# Ultrasonic_Array_8x8.net
KiCad netlist of a schematic drawn in EAGLE
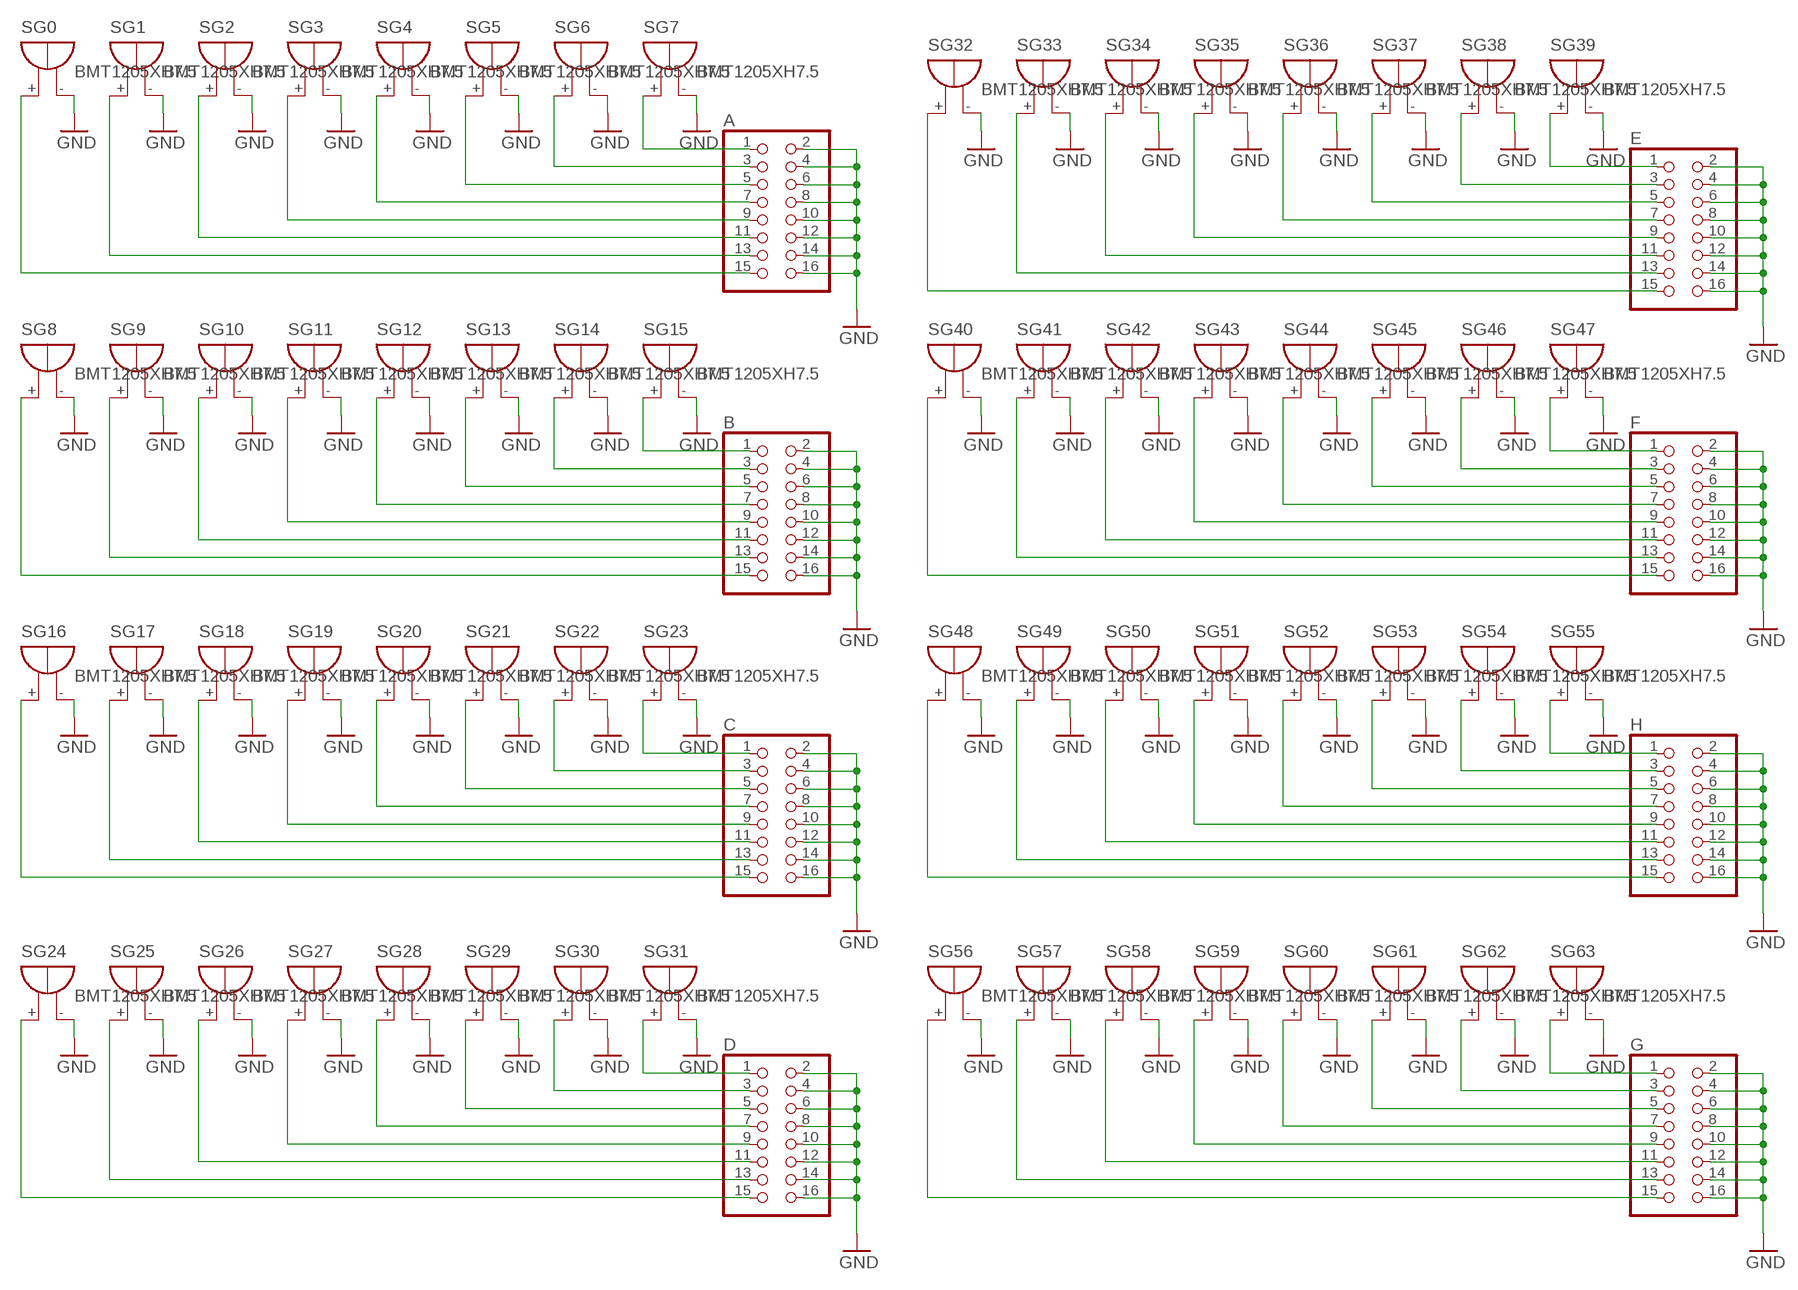
[diagram p0: schematic, sheet 1]

(export (version "E")
  (design (tool "Eeschema 10.0.6"))
  (components
    (comp (ref "A")
      (value "PINHD-2X8")
      (footprint "eagle-import:2X08")
      (libsource (lib "eagle-import") (part "PINHD-2X8"))
    )
    (comp (ref "B")
      (value "PINHD-2X8")
      (footprint "eagle-import:2X08")
      (libsource (lib "eagle-import") (part "PINHD-2X8"))
    )
    (comp (ref "C")
      (value "PINHD-2X8")
      (footprint "eagle-import:2X08")
      (libsource (lib "eagle-import") (part "PINHD-2X8"))
    )
    (comp (ref "D")
      (value "PINHD-2X8")
      (footprint "eagle-import:2X08")
      (libsource (lib "eagle-import") (part "PINHD-2X8"))
    )
    (comp (ref "E")
      (value "PINHD-2X8")
      (footprint "eagle-import:2X08")
      (libsource (lib "eagle-import") (part "PINHD-2X8"))
    )
    (comp (ref "F")
      (value "PINHD-2X8")
      (footprint "eagle-import:2X08")
      (libsource (lib "eagle-import") (part "PINHD-2X8"))
    )
    (comp (ref "G")
      (value "PINHD-2X8")
      (footprint "eagle-import:2X08")
      (libsource (lib "eagle-import") (part "PINHD-2X8"))
    )
    (comp (ref "H")
      (value "PINHD-2X8")
      (footprint "eagle-import:2X08")
      (libsource (lib "eagle-import") (part "PINHD-2X8"))
    )
    (comp (ref "SG0")
      (value "BMT1205XH7.5")
      (footprint "eagle-import:BMT1205XH7.5")
      (libsource (lib "eagle-import") (part "BMT1205XH7.5"))
    )
    (comp (ref "SG1")
      (value "BMT1205XH7.5")
      (footprint "eagle-import:BMT1205XH7.5")
      (libsource (lib "eagle-import") (part "BMT1205XH7.5"))
    )
    (comp (ref "SG2")
      (value "BMT1205XH7.5")
      (footprint "eagle-import:BMT1205XH7.5")
      (libsource (lib "eagle-import") (part "BMT1205XH7.5"))
    )
    (comp (ref "SG3")
      (value "BMT1205XH7.5")
      (footprint "eagle-import:BMT1205XH7.5")
      (libsource (lib "eagle-import") (part "BMT1205XH7.5"))
    )
    (comp (ref "SG4")
      (value "BMT1205XH7.5")
      (footprint "eagle-import:BMT1205XH7.5")
      (libsource (lib "eagle-import") (part "BMT1205XH7.5"))
    )
    (comp (ref "SG5")
      (value "BMT1205XH7.5")
      (footprint "eagle-import:BMT1205XH7.5")
      (libsource (lib "eagle-import") (part "BMT1205XH7.5"))
    )
    (comp (ref "SG6")
      (value "BMT1205XH7.5")
      (footprint "eagle-import:BMT1205XH7.5")
      (libsource (lib "eagle-import") (part "BMT1205XH7.5"))
    )
    (comp (ref "SG7")
      (value "BMT1205XH7.5")
      (footprint "eagle-import:BMT1205XH7.5")
      (libsource (lib "eagle-import") (part "BMT1205XH7.5"))
    )
    (comp (ref "SG8")
      (value "BMT1205XH7.5")
      (footprint "eagle-import:BMT1205XH7.5")
      (libsource (lib "eagle-import") (part "BMT1205XH7.5"))
    )
    (comp (ref "SG9")
      (value "BMT1205XH7.5")
      (footprint "eagle-import:BMT1205XH7.5")
      (libsource (lib "eagle-import") (part "BMT1205XH7.5"))
    )
    (comp (ref "SG10")
      (value "BMT1205XH7.5")
      (footprint "eagle-import:BMT1205XH7.5")
      (libsource (lib "eagle-import") (part "BMT1205XH7.5"))
    )
    (comp (ref "SG11")
      (value "BMT1205XH7.5")
      (footprint "eagle-import:BMT1205XH7.5")
      (libsource (lib "eagle-import") (part "BMT1205XH7.5"))
    )
    (comp (ref "SG12")
      (value "BMT1205XH7.5")
      (footprint "eagle-import:BMT1205XH7.5")
      (libsource (lib "eagle-import") (part "BMT1205XH7.5"))
    )
    (comp (ref "SG13")
      (value "BMT1205XH7.5")
      (footprint "eagle-import:BMT1205XH7.5")
      (libsource (lib "eagle-import") (part "BMT1205XH7.5"))
    )
    (comp (ref "SG14")
      (value "BMT1205XH7.5")
      (footprint "eagle-import:BMT1205XH7.5")
      (libsource (lib "eagle-import") (part "BMT1205XH7.5"))
    )
    (comp (ref "SG15")
      (value "BMT1205XH7.5")
      (footprint "eagle-import:BMT1205XH7.5")
      (libsource (lib "eagle-import") (part "BMT1205XH7.5"))
    )
    (comp (ref "SG16")
      (value "BMT1205XH7.5")
      (footprint "eagle-import:BMT1205XH7.5")
      (libsource (lib "eagle-import") (part "BMT1205XH7.5"))
    )
    (comp (ref "SG17")
      (value "BMT1205XH7.5")
      (footprint "eagle-import:BMT1205XH7.5")
      (libsource (lib "eagle-import") (part "BMT1205XH7.5"))
    )
    (comp (ref "SG18")
      (value "BMT1205XH7.5")
      (footprint "eagle-import:BMT1205XH7.5")
      (libsource (lib "eagle-import") (part "BMT1205XH7.5"))
    )
    (comp (ref "SG19")
      (value "BMT1205XH7.5")
      (footprint "eagle-import:BMT1205XH7.5")
      (libsource (lib "eagle-import") (part "BMT1205XH7.5"))
    )
    (comp (ref "SG20")
      (value "BMT1205XH7.5")
      (footprint "eagle-import:BMT1205XH7.5")
      (libsource (lib "eagle-import") (part "BMT1205XH7.5"))
    )
    (comp (ref "SG21")
      (value "BMT1205XH7.5")
      (footprint "eagle-import:BMT1205XH7.5")
      (libsource (lib "eagle-import") (part "BMT1205XH7.5"))
    )
    (comp (ref "SG22")
      (value "BMT1205XH7.5")
      (footprint "eagle-import:BMT1205XH7.5")
      (libsource (lib "eagle-import") (part "BMT1205XH7.5"))
    )
    (comp (ref "SG23")
      (value "BMT1205XH7.5")
      (footprint "eagle-import:BMT1205XH7.5")
      (libsource (lib "eagle-import") (part "BMT1205XH7.5"))
    )
    (comp (ref "SG24")
      (value "BMT1205XH7.5")
      (footprint "eagle-import:BMT1205XH7.5")
      (libsource (lib "eagle-import") (part "BMT1205XH7.5"))
    )
    (comp (ref "SG25")
      (value "BMT1205XH7.5")
      (footprint "eagle-import:BMT1205XH7.5")
      (libsource (lib "eagle-import") (part "BMT1205XH7.5"))
    )
    (comp (ref "SG26")
      (value "BMT1205XH7.5")
      (footprint "eagle-import:BMT1205XH7.5")
      (libsource (lib "eagle-import") (part "BMT1205XH7.5"))
    )
    (comp (ref "SG27")
      (value "BMT1205XH7.5")
      (footprint "eagle-import:BMT1205XH7.5")
      (libsource (lib "eagle-import") (part "BMT1205XH7.5"))
    )
    (comp (ref "SG28")
      (value "BMT1205XH7.5")
      (footprint "eagle-import:BMT1205XH7.5")
      (libsource (lib "eagle-import") (part "BMT1205XH7.5"))
    )
    (comp (ref "SG29")
      (value "BMT1205XH7.5")
      (footprint "eagle-import:BMT1205XH7.5")
      (libsource (lib "eagle-import") (part "BMT1205XH7.5"))
    )
    (comp (ref "SG30")
      (value "BMT1205XH7.5")
      (footprint "eagle-import:BMT1205XH7.5")
      (libsource (lib "eagle-import") (part "BMT1205XH7.5"))
    )
    (comp (ref "SG31")
      (value "BMT1205XH7.5")
      (footprint "eagle-import:BMT1205XH7.5")
      (libsource (lib "eagle-import") (part "BMT1205XH7.5"))
    )
    (comp (ref "SG32")
      (value "BMT1205XH7.5")
      (footprint "eagle-import:BMT1205XH7.5")
      (libsource (lib "eagle-import") (part "BMT1205XH7.5"))
    )
    (comp (ref "SG33")
      (value "BMT1205XH7.5")
      (footprint "eagle-import:BMT1205XH7.5")
      (libsource (lib "eagle-import") (part "BMT1205XH7.5"))
    )
    (comp (ref "SG34")
      (value "BMT1205XH7.5")
      (footprint "eagle-import:BMT1205XH7.5")
      (libsource (lib "eagle-import") (part "BMT1205XH7.5"))
    )
    (comp (ref "SG35")
      (value "BMT1205XH7.5")
      (footprint "eagle-import:BMT1205XH7.5")
      (libsource (lib "eagle-import") (part "BMT1205XH7.5"))
    )
    (comp (ref "SG36")
      (value "BMT1205XH7.5")
      (footprint "eagle-import:BMT1205XH7.5")
      (libsource (lib "eagle-import") (part "BMT1205XH7.5"))
    )
    (comp (ref "SG37")
      (value "BMT1205XH7.5")
      (footprint "eagle-import:BMT1205XH7.5")
      (libsource (lib "eagle-import") (part "BMT1205XH7.5"))
    )
    (comp (ref "SG38")
      (value "BMT1205XH7.5")
      (footprint "eagle-import:BMT1205XH7.5")
      (libsource (lib "eagle-import") (part "BMT1205XH7.5"))
    )
    (comp (ref "SG39")
      (value "BMT1205XH7.5")
      (footprint "eagle-import:BMT1205XH7.5")
      (libsource (lib "eagle-import") (part "BMT1205XH7.5"))
    )
    (comp (ref "SG40")
      (value "BMT1205XH7.5")
      (footprint "eagle-import:BMT1205XH7.5")
      (libsource (lib "eagle-import") (part "BMT1205XH7.5"))
    )
    (comp (ref "SG41")
      (value "BMT1205XH7.5")
      (footprint "eagle-import:BMT1205XH7.5")
      (libsource (lib "eagle-import") (part "BMT1205XH7.5"))
    )
    (comp (ref "SG42")
      (value "BMT1205XH7.5")
      (footprint "eagle-import:BMT1205XH7.5")
      (libsource (lib "eagle-import") (part "BMT1205XH7.5"))
    )
    (comp (ref "SG43")
      (value "BMT1205XH7.5")
      (footprint "eagle-import:BMT1205XH7.5")
      (libsource (lib "eagle-import") (part "BMT1205XH7.5"))
    )
    (comp (ref "SG44")
      (value "BMT1205XH7.5")
      (footprint "eagle-import:BMT1205XH7.5")
      (libsource (lib "eagle-import") (part "BMT1205XH7.5"))
    )
    (comp (ref "SG45")
      (value "BMT1205XH7.5")
      (footprint "eagle-import:BMT1205XH7.5")
      (libsource (lib "eagle-import") (part "BMT1205XH7.5"))
    )
    (comp (ref "SG46")
      (value "BMT1205XH7.5")
      (footprint "eagle-import:BMT1205XH7.5")
      (libsource (lib "eagle-import") (part "BMT1205XH7.5"))
    )
    (comp (ref "SG47")
      (value "BMT1205XH7.5")
      (footprint "eagle-import:BMT1205XH7.5")
      (libsource (lib "eagle-import") (part "BMT1205XH7.5"))
    )
    (comp (ref "SG48")
      (value "BMT1205XH7.5")
      (footprint "eagle-import:BMT1205XH7.5")
      (libsource (lib "eagle-import") (part "BMT1205XH7.5"))
    )
    (comp (ref "SG49")
      (value "BMT1205XH7.5")
      (footprint "eagle-import:BMT1205XH7.5")
      (libsource (lib "eagle-import") (part "BMT1205XH7.5"))
    )
    (comp (ref "SG50")
      (value "BMT1205XH7.5")
      (footprint "eagle-import:BMT1205XH7.5")
      (libsource (lib "eagle-import") (part "BMT1205XH7.5"))
    )
    (comp (ref "SG51")
      (value "BMT1205XH7.5")
      (footprint "eagle-import:BMT1205XH7.5")
      (libsource (lib "eagle-import") (part "BMT1205XH7.5"))
    )
    (comp (ref "SG52")
      (value "BMT1205XH7.5")
      (footprint "eagle-import:BMT1205XH7.5")
      (libsource (lib "eagle-import") (part "BMT1205XH7.5"))
    )
    (comp (ref "SG53")
      (value "BMT1205XH7.5")
      (footprint "eagle-import:BMT1205XH7.5")
      (libsource (lib "eagle-import") (part "BMT1205XH7.5"))
    )
    (comp (ref "SG54")
      (value "BMT1205XH7.5")
      (footprint "eagle-import:BMT1205XH7.5")
      (libsource (lib "eagle-import") (part "BMT1205XH7.5"))
    )
    (comp (ref "SG55")
      (value "BMT1205XH7.5")
      (footprint "eagle-import:BMT1205XH7.5")
      (libsource (lib "eagle-import") (part "BMT1205XH7.5"))
    )
    (comp (ref "SG56")
      (value "BMT1205XH7.5")
      (footprint "eagle-import:BMT1205XH7.5")
      (libsource (lib "eagle-import") (part "BMT1205XH7.5"))
    )
    (comp (ref "SG57")
      (value "BMT1205XH7.5")
      (footprint "eagle-import:BMT1205XH7.5")
      (libsource (lib "eagle-import") (part "BMT1205XH7.5"))
    )
    (comp (ref "SG58")
      (value "BMT1205XH7.5")
      (footprint "eagle-import:BMT1205XH7.5")
      (libsource (lib "eagle-import") (part "BMT1205XH7.5"))
    )
    (comp (ref "SG59")
      (value "BMT1205XH7.5")
      (footprint "eagle-import:BMT1205XH7.5")
      (libsource (lib "eagle-import") (part "BMT1205XH7.5"))
    )
    (comp (ref "SG60")
      (value "BMT1205XH7.5")
      (footprint "eagle-import:BMT1205XH7.5")
      (libsource (lib "eagle-import") (part "BMT1205XH7.5"))
    )
    (comp (ref "SG61")
      (value "BMT1205XH7.5")
      (footprint "eagle-import:BMT1205XH7.5")
      (libsource (lib "eagle-import") (part "BMT1205XH7.5"))
    )
    (comp (ref "SG62")
      (value "BMT1205XH7.5")
      (footprint "eagle-import:BMT1205XH7.5")
      (libsource (lib "eagle-import") (part "BMT1205XH7.5"))
    )
    (comp (ref "SG63")
      (value "BMT1205XH7.5")
      (footprint "eagle-import:BMT1205XH7.5")
      (libsource (lib "eagle-import") (part "BMT1205XH7.5"))
    )
  )
  (nets
    (net (code "1") (name "GND") (class "Default")
      (node (ref "A") (pin "10") (pinfunction "10_10") (pintype "passive"))
      (node (ref "A") (pin "12") (pinfunction "12_12") (pintype "passive"))
      (node (ref "A") (pin "14") (pinfunction "14_14") (pintype "passive"))
      (node (ref "A") (pin "16") (pinfunction "16_16") (pintype "passive"))
      (node (ref "A") (pin "2") (pinfunction "2_2") (pintype "passive"))
      (node (ref "A") (pin "4") (pinfunction "4_4") (pintype "passive"))
      (node (ref "A") (pin "6") (pinfunction "6_6") (pintype "passive"))
      (node (ref "A") (pin "8") (pinfunction "8_8") (pintype "passive"))
      (node (ref "B") (pin "10") (pinfunction "10_10") (pintype "passive"))
      (node (ref "B") (pin "12") (pinfunction "12_12") (pintype "passive"))
      (node (ref "B") (pin "14") (pinfunction "14_14") (pintype "passive"))
      (node (ref "B") (pin "16") (pinfunction "16_16") (pintype "passive"))
      (node (ref "B") (pin "2") (pinfunction "2_2") (pintype "passive"))
      (node (ref "B") (pin "4") (pinfunction "4_4") (pintype "passive"))
      (node (ref "B") (pin "6") (pinfunction "6_6") (pintype "passive"))
      (node (ref "B") (pin "8") (pinfunction "8_8") (pintype "passive"))
      (node (ref "C") (pin "10") (pinfunction "10_10") (pintype "passive"))
      (node (ref "C") (pin "12") (pinfunction "12_12") (pintype "passive"))
      (node (ref "C") (pin "14") (pinfunction "14_14") (pintype "passive"))
      (node (ref "C") (pin "16") (pinfunction "16_16") (pintype "passive"))
      (node (ref "C") (pin "2") (pinfunction "2_2") (pintype "passive"))
      (node (ref "C") (pin "4") (pinfunction "4_4") (pintype "passive"))
      (node (ref "C") (pin "6") (pinfunction "6_6") (pintype "passive"))
      (node (ref "C") (pin "8") (pinfunction "8_8") (pintype "passive"))
      (node (ref "D") (pin "10") (pinfunction "10_10") (pintype "passive"))
      (node (ref "D") (pin "12") (pinfunction "12_12") (pintype "passive"))
      (node (ref "D") (pin "14") (pinfunction "14_14") (pintype "passive"))
      (node (ref "D") (pin "16") (pinfunction "16_16") (pintype "passive"))
      (node (ref "D") (pin "2") (pinfunction "2_2") (pintype "passive"))
      (node (ref "D") (pin "4") (pinfunction "4_4") (pintype "passive"))
      (node (ref "D") (pin "6") (pinfunction "6_6") (pintype "passive"))
      (node (ref "D") (pin "8") (pinfunction "8_8") (pintype "passive"))
      (node (ref "E") (pin "10") (pinfunction "10_10") (pintype "passive"))
      (node (ref "E") (pin "12") (pinfunction "12_12") (pintype "passive"))
      (node (ref "E") (pin "14") (pinfunction "14_14") (pintype "passive"))
      (node (ref "E") (pin "16") (pinfunction "16_16") (pintype "passive"))
      (node (ref "E") (pin "2") (pinfunction "2_2") (pintype "passive"))
      (node (ref "E") (pin "4") (pinfunction "4_4") (pintype "passive"))
      (node (ref "E") (pin "6") (pinfunction "6_6") (pintype "passive"))
      (node (ref "E") (pin "8") (pinfunction "8_8") (pintype "passive"))
      (node (ref "F") (pin "10") (pinfunction "10_10") (pintype "passive"))
      (node (ref "F") (pin "12") (pinfunction "12_12") (pintype "passive"))
      (node (ref "F") (pin "14") (pinfunction "14_14") (pintype "passive"))
      (node (ref "F") (pin "16") (pinfunction "16_16") (pintype "passive"))
      (node (ref "F") (pin "2") (pinfunction "2_2") (pintype "passive"))
      (node (ref "F") (pin "4") (pinfunction "4_4") (pintype "passive"))
      (node (ref "F") (pin "6") (pinfunction "6_6") (pintype "passive"))
      (node (ref "F") (pin "8") (pinfunction "8_8") (pintype "passive"))
      (node (ref "G") (pin "10") (pinfunction "10_10") (pintype "passive"))
      (node (ref "G") (pin "12") (pinfunction "12_12") (pintype "passive"))
      (node (ref "G") (pin "14") (pinfunction "14_14") (pintype "passive"))
      (node (ref "G") (pin "16") (pinfunction "16_16") (pintype "passive"))
      (node (ref "G") (pin "2") (pinfunction "2_2") (pintype "passive"))
      (node (ref "G") (pin "4") (pinfunction "4_4") (pintype "passive"))
      (node (ref "G") (pin "6") (pinfunction "6_6") (pintype "passive"))
      (node (ref "G") (pin "8") (pinfunction "8_8") (pintype "passive"))
      (node (ref "H") (pin "10") (pinfunction "10_10") (pintype "passive"))
      (node (ref "H") (pin "12") (pinfunction "12_12") (pintype "passive"))
      (node (ref "H") (pin "14") (pinfunction "14_14") (pintype "passive"))
      (node (ref "H") (pin "16") (pinfunction "16_16") (pintype "passive"))
      (node (ref "H") (pin "2") (pinfunction "2_2") (pintype "passive"))
      (node (ref "H") (pin "4") (pinfunction "4_4") (pintype "passive"))
      (node (ref "H") (pin "6") (pinfunction "6_6") (pintype "passive"))
      (node (ref "H") (pin "8") (pinfunction "8_8") (pintype "passive"))
      (node (ref "SG0") (pin "-") (pinfunction "-_-") (pintype "passive"))
      (node (ref "SG1") (pin "-") (pinfunction "-_-") (pintype "passive"))
      (node (ref "SG10") (pin "-") (pinfunction "-_-") (pintype "passive"))
      (node (ref "SG11") (pin "-") (pinfunction "-_-") (pintype "passive"))
      (node (ref "SG12") (pin "-") (pinfunction "-_-") (pintype "passive"))
      (node (ref "SG13") (pin "-") (pinfunction "-_-") (pintype "passive"))
      (node (ref "SG14") (pin "-") (pinfunction "-_-") (pintype "passive"))
      (node (ref "SG15") (pin "-") (pinfunction "-_-") (pintype "passive"))
      (node (ref "SG16") (pin "-") (pinfunction "-_-") (pintype "passive"))
      (node (ref "SG17") (pin "-") (pinfunction "-_-") (pintype "passive"))
      (node (ref "SG18") (pin "-") (pinfunction "-_-") (pintype "passive"))
      (node (ref "SG19") (pin "-") (pinfunction "-_-") (pintype "passive"))
      (node (ref "SG2") (pin "-") (pinfunction "-_-") (pintype "passive"))
      (node (ref "SG20") (pin "-") (pinfunction "-_-") (pintype "passive"))
      (node (ref "SG21") (pin "-") (pinfunction "-_-") (pintype "passive"))
      (node (ref "SG22") (pin "-") (pinfunction "-_-") (pintype "passive"))
      (node (ref "SG23") (pin "-") (pinfunction "-_-") (pintype "passive"))
      (node (ref "SG24") (pin "-") (pinfunction "-_-") (pintype "passive"))
      (node (ref "SG25") (pin "-") (pinfunction "-_-") (pintype "passive"))
      (node (ref "SG26") (pin "-") (pinfunction "-_-") (pintype "passive"))
      (node (ref "SG27") (pin "-") (pinfunction "-_-") (pintype "passive"))
      (node (ref "SG28") (pin "-") (pinfunction "-_-") (pintype "passive"))
      (node (ref "SG29") (pin "-") (pinfunction "-_-") (pintype "passive"))
      (node (ref "SG3") (pin "-") (pinfunction "-_-") (pintype "passive"))
      (node (ref "SG30") (pin "-") (pinfunction "-_-") (pintype "passive"))
      (node (ref "SG31") (pin "-") (pinfunction "-_-") (pintype "passive"))
      (node (ref "SG32") (pin "-") (pinfunction "-_-") (pintype "passive"))
      (node (ref "SG33") (pin "-") (pinfunction "-_-") (pintype "passive"))
      (node (ref "SG34") (pin "-") (pinfunction "-_-") (pintype "passive"))
      (node (ref "SG35") (pin "-") (pinfunction "-_-") (pintype "passive"))
      (node (ref "SG36") (pin "-") (pinfunction "-_-") (pintype "passive"))
      (node (ref "SG37") (pin "-") (pinfunction "-_-") (pintype "passive"))
      (node (ref "SG38") (pin "-") (pinfunction "-_-") (pintype "passive"))
      (node (ref "SG39") (pin "-") (pinfunction "-_-") (pintype "passive"))
      (node (ref "SG4") (pin "-") (pinfunction "-_-") (pintype "passive"))
      (node (ref "SG40") (pin "-") (pinfunction "-_-") (pintype "passive"))
      (node (ref "SG41") (pin "-") (pinfunction "-_-") (pintype "passive"))
      (node (ref "SG42") (pin "-") (pinfunction "-_-") (pintype "passive"))
      (node (ref "SG43") (pin "-") (pinfunction "-_-") (pintype "passive"))
      (node (ref "SG44") (pin "-") (pinfunction "-_-") (pintype "passive"))
      (node (ref "SG45") (pin "-") (pinfunction "-_-") (pintype "passive"))
      (node (ref "SG46") (pin "-") (pinfunction "-_-") (pintype "passive"))
      (node (ref "SG47") (pin "-") (pinfunction "-_-") (pintype "passive"))
      (node (ref "SG48") (pin "-") (pinfunction "-_-") (pintype "passive"))
      (node (ref "SG49") (pin "-") (pinfunction "-_-") (pintype "passive"))
      (node (ref "SG5") (pin "-") (pinfunction "-_-") (pintype "passive"))
      (node (ref "SG50") (pin "-") (pinfunction "-_-") (pintype "passive"))
      (node (ref "SG51") (pin "-") (pinfunction "-_-") (pintype "passive"))
      (node (ref "SG52") (pin "-") (pinfunction "-_-") (pintype "passive"))
      (node (ref "SG53") (pin "-") (pinfunction "-_-") (pintype "passive"))
      (node (ref "SG54") (pin "-") (pinfunction "-_-") (pintype "passive"))
      (node (ref "SG55") (pin "-") (pinfunction "-_-") (pintype "passive"))
      (node (ref "SG56") (pin "-") (pinfunction "-_-") (pintype "passive"))
      (node (ref "SG57") (pin "-") (pinfunction "-_-") (pintype "passive"))
      (node (ref "SG58") (pin "-") (pinfunction "-_-") (pintype "passive"))
      (node (ref "SG59") (pin "-") (pinfunction "-_-") (pintype "passive"))
      (node (ref "SG6") (pin "-") (pinfunction "-_-") (pintype "passive"))
      (node (ref "SG60") (pin "-") (pinfunction "-_-") (pintype "passive"))
      (node (ref "SG61") (pin "-") (pinfunction "-_-") (pintype "passive"))
      (node (ref "SG62") (pin "-") (pinfunction "-_-") (pintype "passive"))
      (node (ref "SG63") (pin "-") (pinfunction "-_-") (pintype "passive"))
      (node (ref "SG7") (pin "-") (pinfunction "-_-") (pintype "passive"))
      (node (ref "SG8") (pin "-") (pinfunction "-_-") (pintype "passive"))
      (node (ref "SG9") (pin "-") (pinfunction "-_-") (pintype "passive"))
    )
    (net (code "2") (name "Net-(A-Pad1)") (class "Default")
      (node (ref "A") (pin "1") (pinfunction "1_1") (pintype "passive"))
      (node (ref "SG7") (pin "+") (pinfunction "+_+") (pintype "passive"))
    )
    (net (code "3") (name "Net-(A-Pad3)") (class "Default")
      (node (ref "A") (pin "3") (pinfunction "3_3") (pintype "passive"))
      (node (ref "SG6") (pin "+") (pinfunction "+_+") (pintype "passive"))
    )
    (net (code "4") (name "Net-(A-Pad5)") (class "Default")
      (node (ref "A") (pin "5") (pinfunction "5_5") (pintype "passive"))
      (node (ref "SG5") (pin "+") (pinfunction "+_+") (pintype "passive"))
    )
    (net (code "5") (name "Net-(A-Pad7)") (class "Default")
      (node (ref "A") (pin "7") (pinfunction "7_7") (pintype "passive"))
      (node (ref "SG4") (pin "+") (pinfunction "+_+") (pintype "passive"))
    )
    (net (code "6") (name "Net-(A-Pad9)") (class "Default")
      (node (ref "A") (pin "9") (pinfunction "9_9") (pintype "passive"))
      (node (ref "SG3") (pin "+") (pinfunction "+_+") (pintype "passive"))
    )
    (net (code "7") (name "Net-(A-Pad11)") (class "Default")
      (node (ref "A") (pin "11") (pinfunction "11_11") (pintype "passive"))
      (node (ref "SG2") (pin "+") (pinfunction "+_+") (pintype "passive"))
    )
    (net (code "8") (name "Net-(A-Pad13)") (class "Default")
      (node (ref "A") (pin "13") (pinfunction "13_13") (pintype "passive"))
      (node (ref "SG1") (pin "+") (pinfunction "+_+") (pintype "passive"))
    )
    (net (code "9") (name "Net-(A-Pad15)") (class "Default")
      (node (ref "A") (pin "15") (pinfunction "15_15") (pintype "passive"))
      (node (ref "SG0") (pin "+") (pinfunction "+_+") (pintype "passive"))
    )
    (net (code "10") (name "Net-(B-Pad1)") (class "Default")
      (node (ref "B") (pin "1") (pinfunction "1_1") (pintype "passive"))
      (node (ref "SG15") (pin "+") (pinfunction "+_+") (pintype "passive"))
    )
    (net (code "11") (name "Net-(B-Pad3)") (class "Default")
      (node (ref "B") (pin "3") (pinfunction "3_3") (pintype "passive"))
      (node (ref "SG14") (pin "+") (pinfunction "+_+") (pintype "passive"))
    )
    (net (code "12") (name "Net-(B-Pad5)") (class "Default")
      (node (ref "B") (pin "5") (pinfunction "5_5") (pintype "passive"))
      (node (ref "SG13") (pin "+") (pinfunction "+_+") (pintype "passive"))
    )
    (net (code "13") (name "Net-(B-Pad7)") (class "Default")
      (node (ref "B") (pin "7") (pinfunction "7_7") (pintype "passive"))
      (node (ref "SG12") (pin "+") (pinfunction "+_+") (pintype "passive"))
    )
    (net (code "14") (name "Net-(B-Pad9)") (class "Default")
      (node (ref "B") (pin "9") (pinfunction "9_9") (pintype "passive"))
      (node (ref "SG11") (pin "+") (pinfunction "+_+") (pintype "passive"))
    )
    (net (code "15") (name "Net-(B-Pad11)") (class "Default")
      (node (ref "B") (pin "11") (pinfunction "11_11") (pintype "passive"))
      (node (ref "SG10") (pin "+") (pinfunction "+_+") (pintype "passive"))
    )
    (net (code "16") (name "Net-(B-Pad13)") (class "Default")
      (node (ref "B") (pin "13") (pinfunction "13_13") (pintype "passive"))
      (node (ref "SG9") (pin "+") (pinfunction "+_+") (pintype "passive"))
    )
    (net (code "17") (name "Net-(B-Pad15)") (class "Default")
      (node (ref "B") (pin "15") (pinfunction "15_15") (pintype "passive"))
      (node (ref "SG8") (pin "+") (pinfunction "+_+") (pintype "passive"))
    )
    (net (code "18") (name "Net-(C-Pad1)") (class "Default")
      (node (ref "C") (pin "1") (pinfunction "1_1") (pintype "passive"))
      (node (ref "SG23") (pin "+") (pinfunction "+_+") (pintype "passive"))
    )
    (net (code "19") (name "Net-(C-Pad3)") (class "Default")
      (node (ref "C") (pin "3") (pinfunction "3_3") (pintype "passive"))
      (node (ref "SG22") (pin "+") (pinfunction "+_+") (pintype "passive"))
    )
    (net (code "20") (name "Net-(C-Pad5)") (class "Default")
      (node (ref "C") (pin "5") (pinfunction "5_5") (pintype "passive"))
      (node (ref "SG21") (pin "+") (pinfunction "+_+") (pintype "passive"))
    )
    (net (code "21") (name "Net-(C-Pad7)") (class "Default")
      (node (ref "C") (pin "7") (pinfunction "7_7") (pintype "passive"))
      (node (ref "SG20") (pin "+") (pinfunction "+_+") (pintype "passive"))
    )
    (net (code "22") (name "Net-(C-Pad9)") (class "Default")
      (node (ref "C") (pin "9") (pinfunction "9_9") (pintype "passive"))
      (node (ref "SG19") (pin "+") (pinfunction "+_+") (pintype "passive"))
    )
    (net (code "23") (name "Net-(C-Pad11)") (class "Default")
      (node (ref "C") (pin "11") (pinfunction "11_11") (pintype "passive"))
      (node (ref "SG18") (pin "+") (pinfunction "+_+") (pintype "passive"))
    )
    (net (code "24") (name "Net-(C-Pad13)") (class "Default")
      (node (ref "C") (pin "13") (pinfunction "13_13") (pintype "passive"))
      (node (ref "SG17") (pin "+") (pinfunction "+_+") (pintype "passive"))
    )
    (net (code "25") (name "Net-(C-Pad15)") (class "Default")
      (node (ref "C") (pin "15") (pinfunction "15_15") (pintype "passive"))
      (node (ref "SG16") (pin "+") (pinfunction "+_+") (pintype "passive"))
    )
    (net (code "26") (name "Net-(D-Pad1)") (class "Default")
      (node (ref "D") (pin "1") (pinfunction "1_1") (pintype "passive"))
      (node (ref "SG31") (pin "+") (pinfunction "+_+") (pintype "passive"))
    )
    (net (code "27") (name "Net-(D-Pad3)") (class "Default")
      (node (ref "D") (pin "3") (pinfunction "3_3") (pintype "passive"))
      (node (ref "SG30") (pin "+") (pinfunction "+_+") (pintype "passive"))
    )
    (net (code "28") (name "Net-(D-Pad5)") (class "Default")
      (node (ref "D") (pin "5") (pinfunction "5_5") (pintype "passive"))
      (node (ref "SG29") (pin "+") (pinfunction "+_+") (pintype "passive"))
    )
    (net (code "29") (name "Net-(D-Pad7)") (class "Default")
      (node (ref "D") (pin "7") (pinfunction "7_7") (pintype "passive"))
      (node (ref "SG28") (pin "+") (pinfunction "+_+") (pintype "passive"))
    )
    (net (code "30") (name "Net-(D-Pad9)") (class "Default")
      (node (ref "D") (pin "9") (pinfunction "9_9") (pintype "passive"))
      (node (ref "SG27") (pin "+") (pinfunction "+_+") (pintype "passive"))
    )
    (net (code "31") (name "Net-(D-Pad11)") (class "Default")
      (node (ref "D") (pin "11") (pinfunction "11_11") (pintype "passive"))
      (node (ref "SG26") (pin "+") (pinfunction "+_+") (pintype "passive"))
    )
    (net (code "32") (name "Net-(D-Pad13)") (class "Default")
      (node (ref "D") (pin "13") (pinfunction "13_13") (pintype "passive"))
      (node (ref "SG25") (pin "+") (pinfunction "+_+") (pintype "passive"))
    )
    (net (code "33") (name "Net-(D-Pad15)") (class "Default")
      (node (ref "D") (pin "15") (pinfunction "15_15") (pintype "passive"))
      (node (ref "SG24") (pin "+") (pinfunction "+_+") (pintype "passive"))
    )
    (net (code "34") (name "Net-(E-Pad1)") (class "Default")
      (node (ref "E") (pin "1") (pinfunction "1_1") (pintype "passive"))
      (node (ref "SG39") (pin "+") (pinfunction "+_+") (pintype "passive"))
    )
    (net (code "35") (name "Net-(E-Pad3)") (class "Default")
      (node (ref "E") (pin "3") (pinfunction "3_3") (pintype "passive"))
      (node (ref "SG38") (pin "+") (pinfunction "+_+") (pintype "passive"))
    )
    (net (code "36") (name "Net-(E-Pad5)") (class "Default")
      (node (ref "E") (pin "5") (pinfunction "5_5") (pintype "passive"))
      (node (ref "SG37") (pin "+") (pinfunction "+_+") (pintype "passive"))
    )
    (net (code "37") (name "Net-(E-Pad7)") (class "Default")
      (node (ref "E") (pin "7") (pinfunction "7_7") (pintype "passive"))
      (node (ref "SG36") (pin "+") (pinfunction "+_+") (pintype "passive"))
    )
    (net (code "38") (name "Net-(E-Pad9)") (class "Default")
      (node (ref "E") (pin "9") (pinfunction "9_9") (pintype "passive"))
      (node (ref "SG35") (pin "+") (pinfunction "+_+") (pintype "passive"))
    )
    (net (code "39") (name "Net-(E-Pad11)") (class "Default")
      (node (ref "E") (pin "11") (pinfunction "11_11") (pintype "passive"))
      (node (ref "SG34") (pin "+") (pinfunction "+_+") (pintype "passive"))
    )
    (net (code "40") (name "Net-(E-Pad13)") (class "Default")
      (node (ref "E") (pin "13") (pinfunction "13_13") (pintype "passive"))
      (node (ref "SG33") (pin "+") (pinfunction "+_+") (pintype "passive"))
    )
    (net (code "41") (name "Net-(E-Pad15)") (class "Default")
      (node (ref "E") (pin "15") (pinfunction "15_15") (pintype "passive"))
      (node (ref "SG32") (pin "+") (pinfunction "+_+") (pintype "passive"))
    )
    (net (code "42") (name "Net-(F-Pad1)") (class "Default")
      (node (ref "F") (pin "1") (pinfunction "1_1") (pintype "passive"))
      (node (ref "SG47") (pin "+") (pinfunction "+_+") (pintype "passive"))
    )
    (net (code "43") (name "Net-(F-Pad3)") (class "Default")
      (node (ref "F") (pin "3") (pinfunction "3_3") (pintype "passive"))
      (node (ref "SG46") (pin "+") (pinfunction "+_+") (pintype "passive"))
    )
    (net (code "44") (name "Net-(F-Pad5)") (class "Default")
      (node (ref "F") (pin "5") (pinfunction "5_5") (pintype "passive"))
      (node (ref "SG45") (pin "+") (pinfunction "+_+") (pintype "passive"))
    )
    (net (code "45") (name "Net-(F-Pad7)") (class "Default")
      (node (ref "F") (pin "7") (pinfunction "7_7") (pintype "passive"))
      (node (ref "SG44") (pin "+") (pinfunction "+_+") (pintype "passive"))
    )
    (net (code "46") (name "Net-(F-Pad9)") (class "Default")
      (node (ref "F") (pin "9") (pinfunction "9_9") (pintype "passive"))
      (node (ref "SG43") (pin "+") (pinfunction "+_+") (pintype "passive"))
    )
    (net (code "47") (name "Net-(F-Pad11)") (class "Default")
      (node (ref "F") (pin "11") (pinfunction "11_11") (pintype "passive"))
      (node (ref "SG42") (pin "+") (pinfunction "+_+") (pintype "passive"))
    )
    (net (code "48") (name "Net-(F-Pad13)") (class "Default")
      (node (ref "F") (pin "13") (pinfunction "13_13") (pintype "passive"))
      (node (ref "SG41") (pin "+") (pinfunction "+_+") (pintype "passive"))
    )
    (net (code "49") (name "Net-(F-Pad15)") (class "Default")
      (node (ref "F") (pin "15") (pinfunction "15_15") (pintype "passive"))
      (node (ref "SG40") (pin "+") (pinfunction "+_+") (pintype "passive"))
    )
    (net (code "50") (name "Net-(G-Pad1)") (class "Default")
      (node (ref "G") (pin "1") (pinfunction "1_1") (pintype "passive"))
      (node (ref "SG63") (pin "+") (pinfunction "+_+") (pintype "passive"))
    )
    (net (code "51") (name "Net-(G-Pad3)") (class "Default")
      (node (ref "G") (pin "3") (pinfunction "3_3") (pintype "passive"))
      (node (ref "SG62") (pin "+") (pinfunction "+_+") (pintype "passive"))
    )
    (net (code "52") (name "Net-(G-Pad5)") (class "Default")
      (node (ref "G") (pin "5") (pinfunction "5_5") (pintype "passive"))
      (node (ref "SG61") (pin "+") (pinfunction "+_+") (pintype "passive"))
    )
    (net (code "53") (name "Net-(G-Pad7)") (class "Default")
      (node (ref "G") (pin "7") (pinfunction "7_7") (pintype "passive"))
      (node (ref "SG60") (pin "+") (pinfunction "+_+") (pintype "passive"))
    )
    (net (code "54") (name "Net-(G-Pad9)") (class "Default")
      (node (ref "G") (pin "9") (pinfunction "9_9") (pintype "passive"))
      (node (ref "SG59") (pin "+") (pinfunction "+_+") (pintype "passive"))
    )
    (net (code "55") (name "Net-(G-Pad11)") (class "Default")
      (node (ref "G") (pin "11") (pinfunction "11_11") (pintype "passive"))
      (node (ref "SG58") (pin "+") (pinfunction "+_+") (pintype "passive"))
    )
    (net (code "56") (name "Net-(G-Pad13)") (class "Default")
      (node (ref "G") (pin "13") (pinfunction "13_13") (pintype "passive"))
      (node (ref "SG57") (pin "+") (pinfunction "+_+") (pintype "passive"))
    )
    (net (code "57") (name "Net-(G-Pad15)") (class "Default")
      (node (ref "G") (pin "15") (pinfunction "15_15") (pintype "passive"))
      (node (ref "SG56") (pin "+") (pinfunction "+_+") (pintype "passive"))
    )
    (net (code "58") (name "Net-(H-Pad1)") (class "Default")
      (node (ref "H") (pin "1") (pinfunction "1_1") (pintype "passive"))
      (node (ref "SG55") (pin "+") (pinfunction "+_+") (pintype "passive"))
    )
    (net (code "59") (name "Net-(H-Pad3)") (class "Default")
      (node (ref "H") (pin "3") (pinfunction "3_3") (pintype "passive"))
      (node (ref "SG54") (pin "+") (pinfunction "+_+") (pintype "passive"))
    )
    (net (code "60") (name "Net-(H-Pad5)") (class "Default")
      (node (ref "H") (pin "5") (pinfunction "5_5") (pintype "passive"))
      (node (ref "SG53") (pin "+") (pinfunction "+_+") (pintype "passive"))
    )
    (net (code "61") (name "Net-(H-Pad7)") (class "Default")
      (node (ref "H") (pin "7") (pinfunction "7_7") (pintype "passive"))
      (node (ref "SG52") (pin "+") (pinfunction "+_+") (pintype "passive"))
    )
    (net (code "62") (name "Net-(H-Pad9)") (class "Default")
      (node (ref "H") (pin "9") (pinfunction "9_9") (pintype "passive"))
      (node (ref "SG51") (pin "+") (pinfunction "+_+") (pintype "passive"))
    )
    (net (code "63") (name "Net-(H-Pad11)") (class "Default")
      (node (ref "H") (pin "11") (pinfunction "11_11") (pintype "passive"))
      (node (ref "SG50") (pin "+") (pinfunction "+_+") (pintype "passive"))
    )
    (net (code "64") (name "Net-(H-Pad13)") (class "Default")
      (node (ref "H") (pin "13") (pinfunction "13_13") (pintype "passive"))
      (node (ref "SG49") (pin "+") (pinfunction "+_+") (pintype "passive"))
    )
    (net (code "65") (name "Net-(H-Pad15)") (class "Default")
      (node (ref "H") (pin "15") (pinfunction "15_15") (pintype "passive"))
      (node (ref "SG48") (pin "+") (pinfunction "+_+") (pintype "passive"))
    )
  )
)
